# RX.net
KiCad netlist of a schematic drawn in Altium Designer
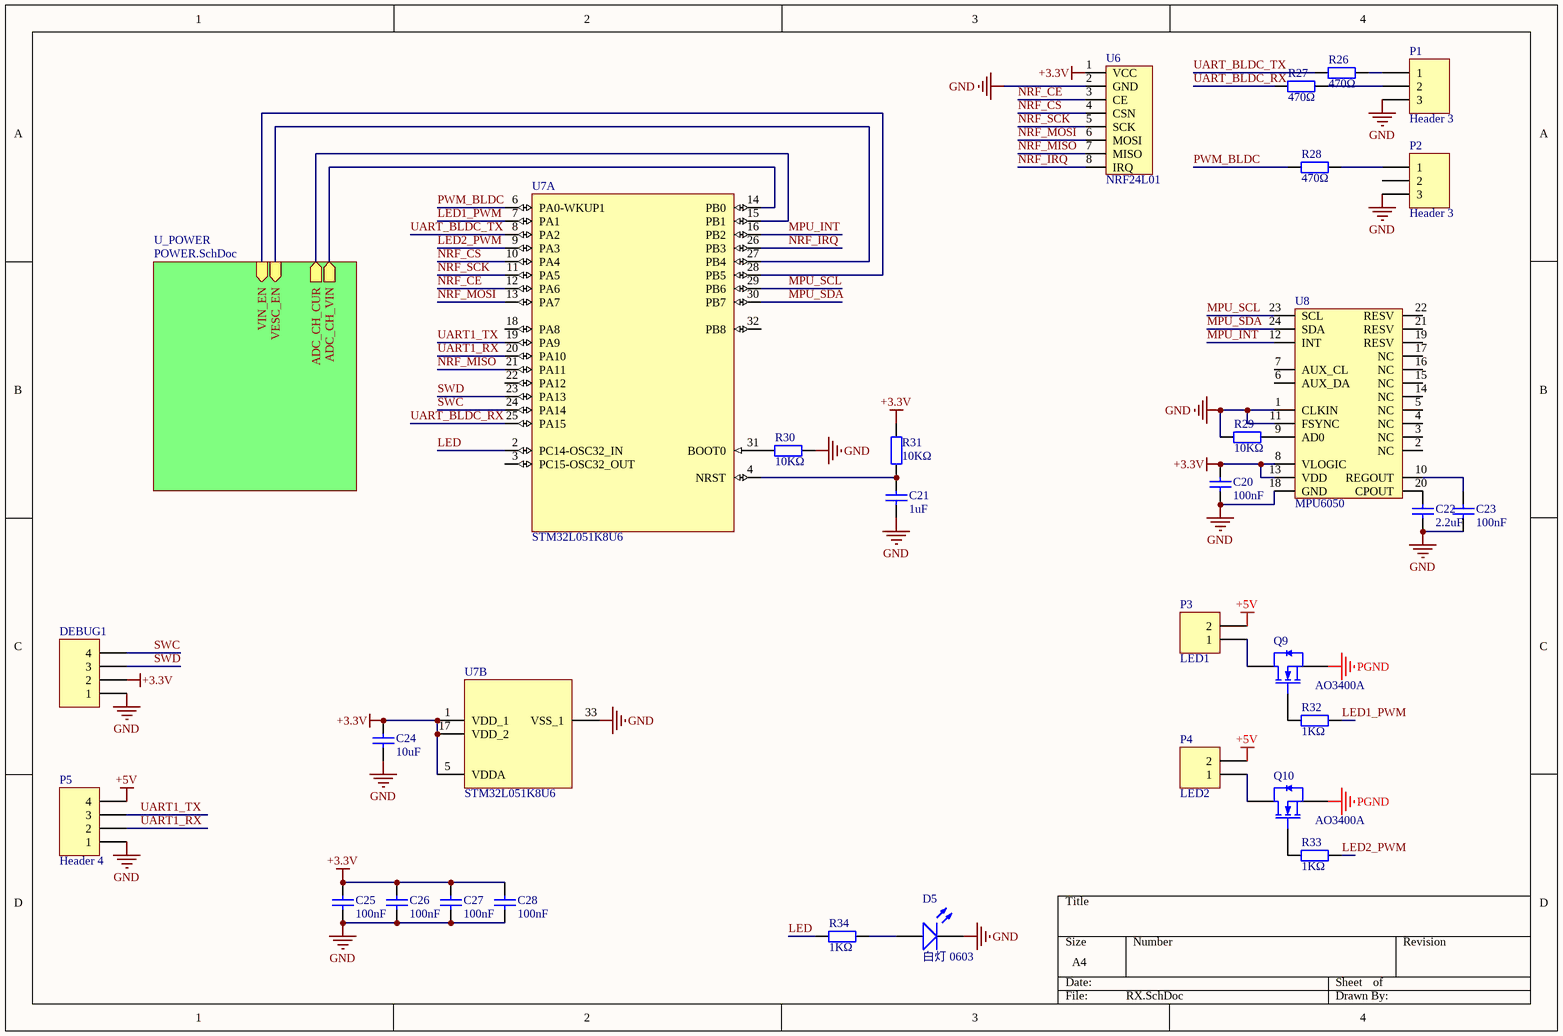
[diagram p0: RX.SchDoc]

(export (version "E")
  (design (tool "Eeschema 10.0.6"))
  (components
    (comp (ref "C20")
      (value "100nF")
      (footprint "0402_C")
      (description "贴片电容")
      (libsource (lib "Miscellaneous Devices LC") (part "0402 100nF (104) 10% 16V"))
    )
    (comp (ref "C21")
      (value "1uF")
      (footprint "0402_C")
      (description "贴片电容")
      (libsource (lib "Miscellaneous Devices LC") (part "0603 1uF (105) 10% 50V"))
    )
    (comp (ref "C22")
      (value "2.2uF")
      (footprint "0402_C")
      (description "贴片电容")
      (libsource (lib "Miscellaneous Devices LC") (part "0603 10uF (106) 10% 10V"))
    )
    (comp (ref "C23")
      (value "100nF")
      (footprint "0402_C")
      (description "贴片电容")
      (libsource (lib "Miscellaneous Devices LC") (part "0402 100nF (104) 10% 16V"))
    )
    (comp (ref "C24")
      (value "10uF")
      (footprint "0603_C")
      (description "贴片电容")
      (libsource (lib "Miscellaneous Devices LC") (part "0603 10uF (106) 10% 10V"))
    )
    (comp (ref "C25")
      (value "100nF")
      (footprint "0402_C")
      (description "贴片电容")
      (libsource (lib "Miscellaneous Devices LC") (part "0402 100nF (104) 10% 16V"))
    )
    (comp (ref "C26")
      (value "100nF")
      (footprint "0402_C")
      (description "贴片电容")
      (libsource (lib "Miscellaneous Devices LC") (part "0402 100nF (104) 10% 16V"))
    )
    (comp (ref "C27")
      (value "100nF")
      (footprint "0402_C")
      (description "贴片电容")
      (libsource (lib "Miscellaneous Devices LC") (part "0402 100nF (104) 10% 16V"))
    )
    (comp (ref "C28")
      (value "100nF")
      (footprint "0402_C")
      (description "贴片电容")
      (libsource (lib "Miscellaneous Devices LC") (part "0402 100nF (104) 10% 16V"))
    )
    (comp (ref "D5")
      (value "白灯 0603")
      (footprint "0603_LED_S1")
      (description "发光二极管")
      (libsource (lib "Miscellaneous Devices LC") (part "0603 白灯"))
    )
    (comp (ref "DEBUG1")
      (value "Header 4")
      (footprint "HDR2.54-LI-4P")
      (description "Header, 4-Pin")
      (fields (field (name "PUBLISHER") "Altium Limited"))
      (libsource (lib "Miscellaneous Connectors") (part "Header 4"))
    )
    (comp (ref "P1")
      (value "Header 3")
      (footprint "HDR2.54-LI-3P")
      (description "Header, 3-Pin")
      (fields (field (name "PUBLISHER") "Altium Limited"))
      (libsource (lib "Miscellaneous Connectors") (part "Header 3"))
    )
    (comp (ref "P2")
      (value "Header 3")
      (footprint "HDR2.54-LI-3P")
      (description "Header, 3-Pin")
      (fields (field (name "PUBLISHER") "Altium Limited"))
      (libsource (lib "Miscellaneous Connectors") (part "Header 3"))
    )
    (comp (ref "P3")
      (value "LED1")
      (footprint "HDR1X2")
      (description "Header, 2-Pin")
      (fields (field (name "PUBLISHER") "Altium Limited"))
      (libsource (lib "Miscellaneous Connectors") (part "Header 2"))
    )
    (comp (ref "P4")
      (value "LED2")
      (footprint "HDR1X2")
      (description "Header, 2-Pin")
      (fields (field (name "PUBLISHER") "Altium Limited"))
      (libsource (lib "Miscellaneous Connectors") (part "Header 2"))
    )
    (comp (ref "P5")
      (value "Header 4")
      (footprint "HDR2.54-LI-4P")
      (description "Header, 4-Pin")
      (fields (field (name "PUBLISHER") "Altium Limited"))
      (libsource (lib "Miscellaneous Connectors") (part "Header 4"))
    )
    (comp (ref "Q9")
      (value "AO3400A")
      (footprint "SOT-23-3L")
      (description "MOS(场效应管)")
      (libsource (lib "Miscellaneous Devices LC") (part "AO3400A N道沟 X0YV1T SOT-23"))
    )
    (comp (ref "Q10")
      (value "AO3400A")
      (footprint "SOT-23-3L")
      (description "MOS(场效应管)")
      (libsource (lib "Miscellaneous Devices LC") (part "AO3400A N道沟 X0YV1T SOT-23"))
    )
    (comp (ref "R26")
      (value "470Ω")
      (footprint "0402_R")
      (description "贴片电阻")
      (libsource (lib "Miscellaneous Devices LC") (part "0402 470Ω (4700) 1%"))
    )
    (comp (ref "R27")
      (value "470Ω")
      (footprint "0402_R")
      (description "贴片电阻")
      (libsource (lib "Miscellaneous Devices LC") (part "0402 470Ω (4700) 1%"))
    )
    (comp (ref "R28")
      (value "470Ω")
      (footprint "0402_R")
      (description "贴片电阻")
      (libsource (lib "Miscellaneous Devices LC") (part "0402 470Ω (4700) 1%"))
    )
    (comp (ref "R29")
      (value "10KΩ")
      (footprint "0402_R")
      (description "贴片电阻")
      (libsource (lib "Miscellaneous Devices LC") (part "0402 10KΩ (1002) 1%"))
    )
    (comp (ref "R30")
      (value "10KΩ")
      (footprint "0402_R")
      (description "贴片电阻")
      (libsource (lib "") (part "0402 10KΩ (1002) 1%_2"))
    )
    (comp (ref "R31")
      (value "10KΩ")
      (footprint "0402_R")
      (description "贴片电阻")
      (libsource (lib "") (part "0402 10KΩ (1002) 1%_1"))
    )
    (comp (ref "R32")
      (value "1KΩ")
      (footprint "0402_R")
      (description "贴片电阻")
      (libsource (lib "Miscellaneous Devices LC") (part "0402 1KΩ (1001) 1%"))
    )
    (comp (ref "R33")
      (value "1KΩ")
      (footprint "0402_R")
      (description "贴片电阻")
      (libsource (lib "Miscellaneous Devices LC") (part "0402 1KΩ (1001) 1%"))
    )
    (comp (ref "R34")
      (value "1KΩ")
      (footprint "0402_R")
      (description "贴片电阻")
      (libsource (lib "Miscellaneous Devices LC") (part "0402 1KΩ (1001) 1%"))
    )
    (comp (ref "U6")
      (value "NRF24L01")
      (footprint "miniNRF24L01")
      (libsource (lib "MySchlib") (part "NRF24L01"))
    )
    (comp (ref "U7")
      (value "STM32L051K8U6")
      (footprint "UFQFPN32-5x5mm")
      (description "ARM")
      (libsource (lib "MySchlib") (part "STM32L051K8U6"))
    )
    (comp (ref "U8")
      (value "MPU6050")
      (footprint "Miscellaneous Devices LC:QFN-24_4x4x05P")
      (description "9轴运动处理传感器")
      (libsource (lib "MySchlib") (part "MPU6050"))
    )
  )
  (nets
    (net (code "1") (name "+3.3V") (class "Default")
      (node (ref "C20") (pin "2") (pinfunction "2_2") (pintype "passive"))
      (node (ref "C24") (pin "2") (pinfunction "2_2") (pintype "passive"))
      (node (ref "C25") (pin "2") (pinfunction "2_2") (pintype "passive"))
      (node (ref "C26") (pin "2") (pinfunction "2_2") (pintype "passive"))
      (node (ref "C27") (pin "2") (pinfunction "2_2") (pintype "passive"))
      (node (ref "C28") (pin "2") (pinfunction "2_2") (pintype "passive"))
      (node (ref "DEBUG1") (pin "2") (pinfunction "2_2") (pintype "passive"))
      (node (ref "R31") (pin "2") (pinfunction "2_2") (pintype "passive"))
      (node (ref "U6") (pin "1") (pinfunction "VCC_1") (pintype "passive"))
      (node (ref "U7") (pin "1") (pinfunction "VDD_1_1") (pintype "power_in"))
      (node (ref "U7") (pin "17") (pinfunction "VDD_2_17") (pintype "power_in"))
      (node (ref "U7") (pin "5") (pinfunction "VDDA_5") (pintype "power_in"))
      (node (ref "U8") (pin "13") (pinfunction "VDD_13") (pintype "passive"))
      (node (ref "U8") (pin "8") (pinfunction "VLOGIC_8") (pintype "passive"))
    )
    (net (code "2") (name "+5V") (class "Default")
      (node (ref "P3") (pin "2") (pinfunction "2_2") (pintype "passive"))
      (node (ref "P4") (pin "2") (pinfunction "2_2") (pintype "passive"))
      (node (ref "P5") (pin "4") (pinfunction "4_4") (pintype "passive"))
    )
    (net (code "3") (name "/ADC_CH_CUR") (class "Default")
      (node (ref "U7") (pin "15") (pinfunction "PB1_15") (pintype "bidirectional"))
    )
    (net (code "4") (name "/ADC_CH_VIN") (class "Default")
      (node (ref "U7") (pin "14") (pinfunction "PB0_14") (pintype "bidirectional"))
    )
    (net (code "5") (name "/LED") (class "Default")
      (node (ref "R34") (pin "1") (pinfunction "1_1") (pintype "passive"))
      (node (ref "U7") (pin "2") (pinfunction "PC14-OSC32_IN_2") (pintype "bidirectional"))
    )
    (net (code "6") (name "/LED1_PWM") (class "Default")
      (node (ref "R32") (pin "2") (pinfunction "2_2") (pintype "passive"))
      (node (ref "U7") (pin "7") (pinfunction "PA1_7") (pintype "bidirectional"))
    )
    (net (code "7") (name "/LED2_PWM") (class "Default")
      (node (ref "R33") (pin "2") (pinfunction "2_2") (pintype "passive"))
      (node (ref "U7") (pin "9") (pinfunction "PA3_9") (pintype "bidirectional"))
    )
    (net (code "8") (name "/MPU_INT") (class "Default")
      (node (ref "U7") (pin "16") (pinfunction "PB2_16") (pintype "bidirectional"))
      (node (ref "U8") (pin "12") (pinfunction "INT_12") (pintype "passive"))
    )
    (net (code "9") (name "/MPU_SCL") (class "Default")
      (node (ref "U7") (pin "29") (pinfunction "PB6_29") (pintype "bidirectional"))
      (node (ref "U8") (pin "23") (pinfunction "SCL_23") (pintype "passive"))
    )
    (net (code "10") (name "/MPU_SDA") (class "Default")
      (node (ref "U7") (pin "30") (pinfunction "PB7_30") (pintype "bidirectional"))
      (node (ref "U8") (pin "24") (pinfunction "SDA_24") (pintype "passive"))
    )
    (net (code "11") (name "/NRF_CE") (class "Default")
      (node (ref "U6") (pin "3") (pinfunction "CE_3") (pintype "passive"))
      (node (ref "U7") (pin "12") (pinfunction "PA6_12") (pintype "bidirectional"))
    )
    (net (code "12") (name "/NRF_CS") (class "Default")
      (node (ref "U6") (pin "4") (pinfunction "CSN_4") (pintype "passive"))
      (node (ref "U7") (pin "10") (pinfunction "PA4_10") (pintype "bidirectional"))
    )
    (net (code "13") (name "/NRF_IRQ") (class "Default")
      (node (ref "U6") (pin "8") (pinfunction "IRQ_8") (pintype "passive"))
      (node (ref "U7") (pin "26") (pinfunction "PB3_26") (pintype "bidirectional"))
    )
    (net (code "14") (name "/NRF_MISO") (class "Default")
      (node (ref "U6") (pin "7") (pinfunction "MISO_7") (pintype "passive"))
      (node (ref "U7") (pin "21") (pinfunction "PA11_21") (pintype "bidirectional"))
    )
    (net (code "15") (name "/NRF_MOSI") (class "Default")
      (node (ref "U6") (pin "6") (pinfunction "MOSI_6") (pintype "passive"))
      (node (ref "U7") (pin "13") (pinfunction "PA7_13") (pintype "bidirectional"))
    )
    (net (code "16") (name "/NRF_SCK") (class "Default")
      (node (ref "U6") (pin "5") (pinfunction "SCK_5") (pintype "passive"))
      (node (ref "U7") (pin "11") (pinfunction "PA5_11") (pintype "bidirectional"))
    )
    (net (code "17") (name "/PWM_BLDC") (class "Default")
      (node (ref "R28") (pin "1") (pinfunction "1_1") (pintype "passive"))
      (node (ref "U7") (pin "6") (pinfunction "PA0-WKUP1_6") (pintype "bidirectional"))
    )
    (net (code "18") (name "/SWC") (class "Default")
      (node (ref "DEBUG1") (pin "4") (pinfunction "4_4") (pintype "passive"))
      (node (ref "U7") (pin "24") (pinfunction "PA14_24") (pintype "bidirectional"))
    )
    (net (code "19") (name "/SWD") (class "Default")
      (node (ref "DEBUG1") (pin "3") (pinfunction "3_3") (pintype "passive"))
      (node (ref "U7") (pin "23") (pinfunction "PA13_23") (pintype "bidirectional"))
    )
    (net (code "20") (name "/UART1_RX") (class "Default")
      (node (ref "P5") (pin "2") (pinfunction "2_2") (pintype "passive"))
      (node (ref "U7") (pin "20") (pinfunction "PA10_20") (pintype "bidirectional"))
    )
    (net (code "21") (name "/UART1_TX") (class "Default")
      (node (ref "P5") (pin "3") (pinfunction "3_3") (pintype "passive"))
      (node (ref "U7") (pin "19") (pinfunction "PA9_19") (pintype "bidirectional"))
    )
    (net (code "22") (name "/UART_BLDC_RX") (class "Default")
      (node (ref "R27") (pin "1") (pinfunction "1_1") (pintype "passive"))
      (node (ref "U7") (pin "25") (pinfunction "PA15_25") (pintype "bidirectional"))
    )
    (net (code "23") (name "/UART_BLDC_TX") (class "Default")
      (node (ref "R26") (pin "1") (pinfunction "1_1") (pintype "passive"))
      (node (ref "U7") (pin "8") (pinfunction "PA2_8") (pintype "bidirectional"))
    )
    (net (code "24") (name "/VESC_EN") (class "Default")
      (node (ref "U7") (pin "27") (pinfunction "PB4_27") (pintype "bidirectional"))
    )
    (net (code "25") (name "/VIN_EN") (class "Default")
      (node (ref "U7") (pin "28") (pinfunction "PB5_28") (pintype "bidirectional"))
    )
    (net (code "26") (name "GND") (class "Default")
      (node (ref "C20") (pin "1") (pinfunction "1_1") (pintype "passive"))
      (node (ref "C21") (pin "1") (pinfunction "1_1") (pintype "passive"))
      (node (ref "C22") (pin "1") (pinfunction "1_1") (pintype "passive"))
      (node (ref "C23") (pin "1") (pinfunction "1_1") (pintype "passive"))
      (node (ref "C24") (pin "1") (pinfunction "1_1") (pintype "passive"))
      (node (ref "C25") (pin "1") (pinfunction "1_1") (pintype "passive"))
      (node (ref "C26") (pin "1") (pinfunction "1_1") (pintype "passive"))
      (node (ref "C27") (pin "1") (pinfunction "1_1") (pintype "passive"))
      (node (ref "C28") (pin "1") (pinfunction "1_1") (pintype "passive"))
      (node (ref "D5") (pin "K") (pinfunction "K_K") (pintype "passive"))
      (node (ref "DEBUG1") (pin "1") (pinfunction "1_1") (pintype "passive"))
      (node (ref "P1") (pin "3") (pinfunction "3_3") (pintype "passive"))
      (node (ref "P2") (pin "3") (pinfunction "3_3") (pintype "passive"))
      (node (ref "P5") (pin "1") (pinfunction "1_1") (pintype "passive"))
      (node (ref "R29") (pin "1") (pinfunction "1_1") (pintype "passive"))
      (node (ref "R30") (pin "1") (pinfunction "1_1") (pintype "passive"))
      (node (ref "U6") (pin "2") (pinfunction "GND_2") (pintype "passive"))
      (node (ref "U7") (pin "33") (pinfunction "VSS_1_33") (pintype "power_in"))
      (node (ref "U8") (pin "1") (pinfunction "CLKIN_1") (pintype "passive"))
      (node (ref "U8") (pin "11") (pinfunction "FSYNC_11") (pintype "passive"))
      (node (ref "U8") (pin "18") (pinfunction "GND_18") (pintype "passive"))
    )
    (net (code "27") (name "Net-(D5-PadA)") (class "Default")
      (node (ref "D5") (pin "A") (pinfunction "A_A") (pintype "passive"))
      (node (ref "R34") (pin "2") (pinfunction "2_2") (pintype "passive"))
    )
    (net (code "28") (name "Net-(P1-Pad1)") (class "Default")
      (node (ref "P1") (pin "1") (pinfunction "1_1") (pintype "passive"))
      (node (ref "R26") (pin "2") (pinfunction "2_2") (pintype "passive"))
    )
    (net (code "29") (name "Net-(P1-Pad2)") (class "Default")
      (node (ref "P1") (pin "2") (pinfunction "2_2") (pintype "passive"))
      (node (ref "R27") (pin "2") (pinfunction "2_2") (pintype "passive"))
    )
    (net (code "30") (name "Net-(P2-Pad1)") (class "Default")
      (node (ref "P2") (pin "1") (pinfunction "1_1") (pintype "passive"))
      (node (ref "R28") (pin "2") (pinfunction "2_2") (pintype "passive"))
    )
    (net (code "31") (name "Net-(Q9-D)") (class "Default")
      (node (ref "P3") (pin "1") (pinfunction "1_1") (pintype "passive"))
      (node (ref "Q9") (pin "3") (pinfunction "D_3") (pintype "passive"))
    )
    (net (code "32") (name "Net-(Q9-G)") (class "Default")
      (node (ref "Q9") (pin "1") (pinfunction "G_1") (pintype "passive"))
      (node (ref "R32") (pin "1") (pinfunction "1_1") (pintype "passive"))
    )
    (net (code "33") (name "Net-(Q10-D)") (class "Default")
      (node (ref "P4") (pin "1") (pinfunction "1_1") (pintype "passive"))
      (node (ref "Q10") (pin "3") (pinfunction "D_3") (pintype "passive"))
    )
    (net (code "34") (name "Net-(Q10-G)") (class "Default")
      (node (ref "Q10") (pin "1") (pinfunction "G_1") (pintype "passive"))
      (node (ref "R33") (pin "1") (pinfunction "1_1") (pintype "passive"))
    )
    (net (code "35") (name "Net-(U7A-BOOT0)") (class "Default")
      (node (ref "R30") (pin "2") (pinfunction "2_2") (pintype "passive"))
      (node (ref "U7") (pin "31") (pinfunction "BOOT0_31") (pintype "input"))
    )
    (net (code "36") (name "Net-(U7A-NRST)") (class "Default")
      (node (ref "C21") (pin "2") (pinfunction "2_2") (pintype "passive"))
      (node (ref "R31") (pin "1") (pinfunction "1_1") (pintype "passive"))
      (node (ref "U7") (pin "4") (pinfunction "NRST_4") (pintype "bidirectional"))
    )
    (net (code "37") (name "Net-(U8-AD0)") (class "Default")
      (node (ref "R29") (pin "2") (pinfunction "2_2") (pintype "passive"))
      (node (ref "U8") (pin "9") (pinfunction "AD0_9") (pintype "passive"))
    )
    (net (code "38") (name "Net-(U8-CPOUT)") (class "Default")
      (node (ref "C22") (pin "2") (pinfunction "2_2") (pintype "passive"))
      (node (ref "U8") (pin "20") (pinfunction "CPOUT_20") (pintype "passive"))
    )
    (net (code "39") (name "Net-(U8-REGOUT)") (class "Default")
      (node (ref "C23") (pin "2") (pinfunction "2_2") (pintype "passive"))
      (node (ref "U8") (pin "10") (pinfunction "REGOUT_10") (pintype "passive"))
    )
    (net (code "40") (name "PGND") (class "Default")
      (node (ref "Q10") (pin "2") (pinfunction "S_2") (pintype "passive"))
      (node (ref "Q9") (pin "2") (pinfunction "S_2") (pintype "passive"))
    )
    (net (code "41") (name "unconnected-(P2-Pad2)") (class "Default")
      (node (ref "P2") (pin "2") (pinfunction "2_2") (pintype "passive"))
    )
    (net (code "42") (name "unconnected-(U7A-PA8-Pad18)") (class "Default")
      (node (ref "U7") (pin "18") (pinfunction "PA8_18") (pintype "bidirectional"))
    )
    (net (code "43") (name "unconnected-(U7A-PA12-Pad22)") (class "Default")
      (node (ref "U7") (pin "22") (pinfunction "PA12_22") (pintype "bidirectional"))
    )
    (net (code "44") (name "unconnected-(U7A-PB8-Pad32)") (class "Default")
      (node (ref "U7") (pin "32") (pinfunction "PB8_32") (pintype "bidirectional"))
    )
    (net (code "45") (name "unconnected-(U7A-PC15-OSC32_OUT-Pad3)") (class "Default")
      (node (ref "U7") (pin "3") (pinfunction "PC15-OSC32_OUT_3") (pintype "bidirectional"))
    )
    (net (code "46") (name "unconnected-(U8-AUX_CL-Pad7)") (class "Default")
      (node (ref "U8") (pin "7") (pinfunction "AUX_CL_7") (pintype "passive"))
    )
    (net (code "47") (name "unconnected-(U8-AUX_DA-Pad6)") (class "Default")
      (node (ref "U8") (pin "6") (pinfunction "AUX_DA_6") (pintype "passive"))
    )
    (net (code "48") (name "unconnected-(U8-NC-Pad2)") (class "Default")
      (node (ref "U8") (pin "2") (pinfunction "NC_2") (pintype "passive"))
    )
    (net (code "49") (name "unconnected-(U8-NC-Pad3)") (class "Default")
      (node (ref "U8") (pin "3") (pinfunction "NC_3") (pintype "passive"))
    )
    (net (code "50") (name "unconnected-(U8-NC-Pad4)") (class "Default")
      (node (ref "U8") (pin "4") (pinfunction "NC_4") (pintype "passive"))
    )
    (net (code "51") (name "unconnected-(U8-NC-Pad5)") (class "Default")
      (node (ref "U8") (pin "5") (pinfunction "NC_5") (pintype "passive"))
    )
    (net (code "52") (name "unconnected-(U8-NC-Pad14)") (class "Default")
      (node (ref "U8") (pin "14") (pinfunction "NC_14") (pintype "passive"))
    )
    (net (code "53") (name "unconnected-(U8-NC-Pad15)") (class "Default")
      (node (ref "U8") (pin "15") (pinfunction "NC_15") (pintype "passive"))
    )
    (net (code "54") (name "unconnected-(U8-NC-Pad16)") (class "Default")
      (node (ref "U8") (pin "16") (pinfunction "NC_16") (pintype "passive"))
    )
    (net (code "55") (name "unconnected-(U8-NC-Pad17)") (class "Default")
      (node (ref "U8") (pin "17") (pinfunction "NC_17") (pintype "passive"))
    )
    (net (code "56") (name "unconnected-(U8-RESV-Pad19)") (class "Default")
      (node (ref "U8") (pin "19") (pinfunction "RESV_19") (pintype "passive"))
    )
    (net (code "57") (name "unconnected-(U8-RESV-Pad21)") (class "Default")
      (node (ref "U8") (pin "21") (pinfunction "RESV_21") (pintype "passive"))
    )
    (net (code "58") (name "unconnected-(U8-RESV-Pad22)") (class "Default")
      (node (ref "U8") (pin "22") (pinfunction "RESV_22") (pintype "passive"))
    )
  )
)
